# 10_-_Isolation.net
KiCad netlist of a schematic drawn in Altium Designer
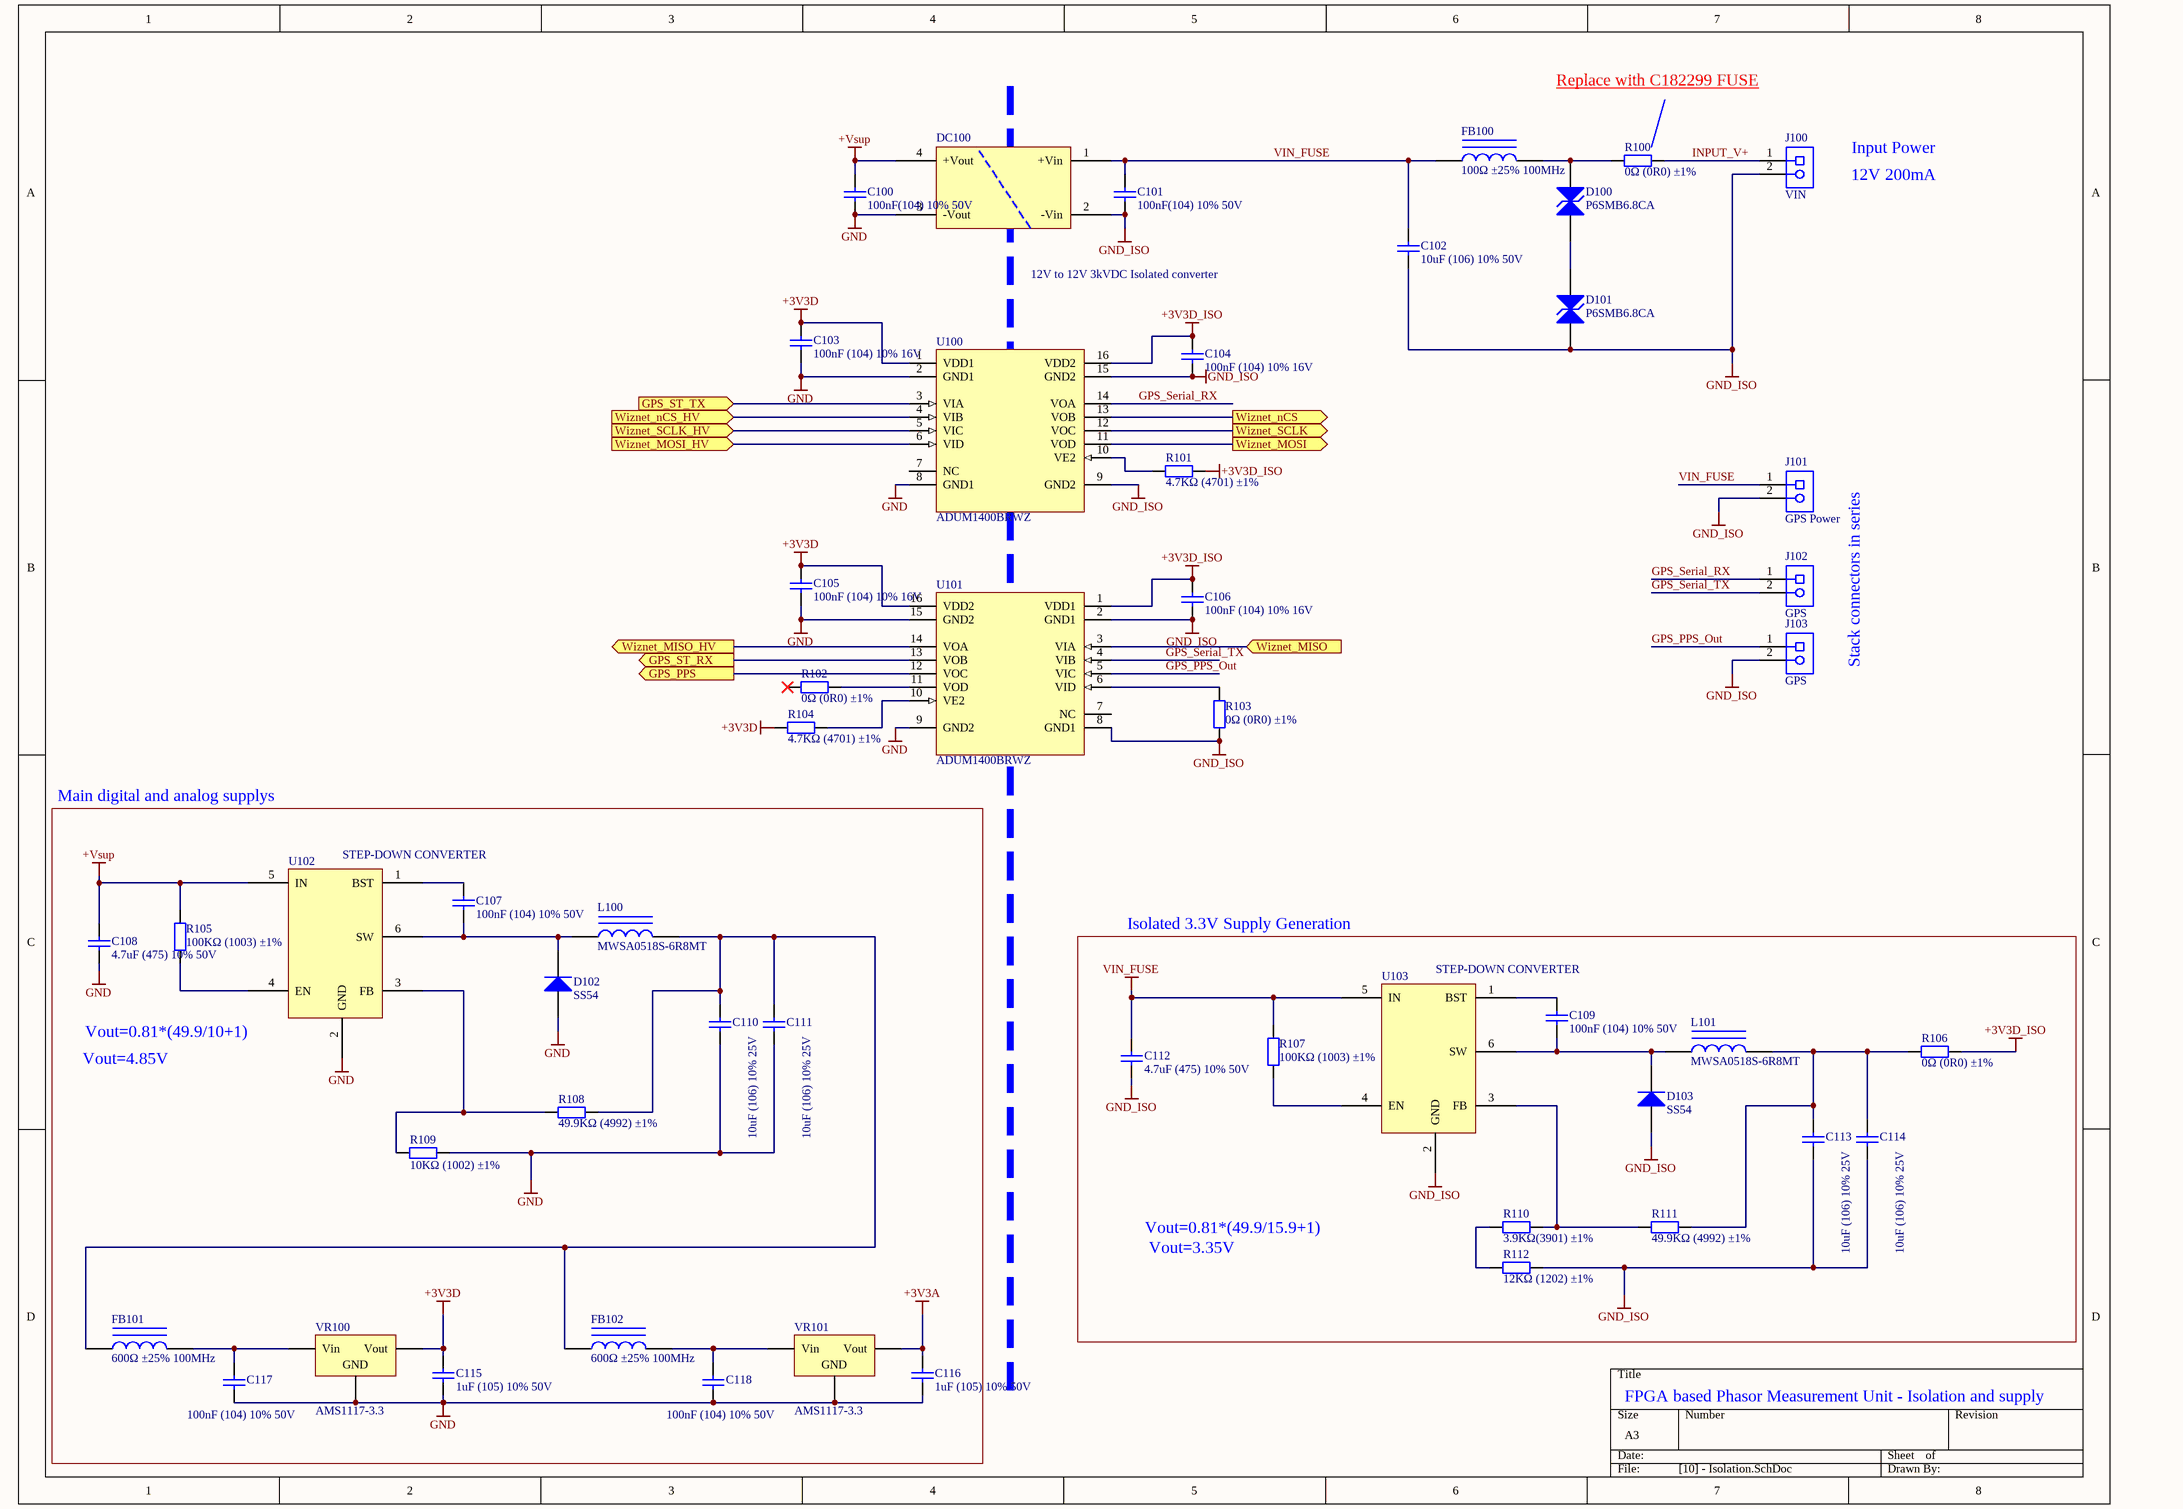
[diagram p0: [10] - Isolation.SchDoc]

(export (version "E")
  (design (tool "Eeschema 10.0.6"))
  (components
    (comp (ref "C100")
      (value "100nF(104) 10% 50V")
      (footprint "0805_C")
      (description "贴片电容")
      (libsource (lib "Cap") (part "0805 100nF(104) 10% 50V"))
    )
    (comp (ref "C101")
      (value "100nF(104) 10% 50V")
      (footprint "0805_C")
      (description "贴片电容")
      (libsource (lib "Cap") (part "0805 100nF(104) 10% 50V"))
    )
    (comp (ref "C102")
      (value "10uF (106) 10% 50V")
      (footprint "1206_C")
      (description "贴片电容")
      (libsource (lib "Cap") (part "1206 10uF (106) 10% 50V"))
    )
    (comp (ref "C103")
      (value "100nF (104) 10% 16V")
      (footprint "0402_C")
      (description "贴片电容")
      (libsource (lib "Cap") (part "0402 100nF (104) 10% 16V"))
    )
    (comp (ref "C104")
      (value "100nF (104) 10% 16V")
      (footprint "0402_C")
      (description "贴片电容")
      (libsource (lib "Cap") (part "0402 100nF (104) 10% 16V"))
    )
    (comp (ref "C105")
      (value "100nF (104) 10% 16V")
      (footprint "0402_C")
      (description "贴片电容")
      (libsource (lib "Cap") (part "0402 100nF (104) 10% 16V"))
    )
    (comp (ref "C106")
      (value "100nF (104) 10% 16V")
      (footprint "0402_C")
      (description "贴片电容")
      (libsource (lib "Cap") (part "0402 100nF (104) 10% 16V"))
    )
    (comp (ref "C107")
      (value "100nF (104) 10% 50V")
      (footprint "0603_C")
      (description "贴片电容")
      (libsource (lib "Cap") (part "0603 100nF (104) 10% 50V"))
    )
    (comp (ref "C108")
      (value "4.7uF (475) 10% 50V")
      (footprint "1206_C")
      (description "贴片电容")
      (libsource (lib "Cap") (part "1206 4.7uF (475) 10% 50V"))
    )
    (comp (ref "C109")
      (value "100nF (104) 10% 50V")
      (footprint "0603_C")
      (description "贴片电容")
      (libsource (lib "Cap") (part "0603 100nF (104) 10% 50V"))
    )
    (comp (ref "C110")
      (value "10uF (106) 10% 25V")
      (footprint "0805_C")
      (description "贴片电容")
      (libsource (lib "Cap") (part "0805 10uF (106) 10% 25V"))
    )
    (comp (ref "C111")
      (value "10uF (106) 10% 25V")
      (footprint "0805_C")
      (description "贴片电容")
      (libsource (lib "Cap") (part "0805 10uF (106) 10% 25V"))
    )
    (comp (ref "C112")
      (value "4.7uF (475) 10% 50V")
      (footprint "1206_C")
      (description "贴片电容")
      (libsource (lib "Cap") (part "1206 4.7uF (475) 10% 50V"))
    )
    (comp (ref "C113")
      (value "10uF (106) 10% 25V")
      (footprint "0805_C")
      (description "贴片电容")
      (libsource (lib "Cap") (part "0805 10uF (106) 10% 25V"))
    )
    (comp (ref "C114")
      (value "10uF (106) 10% 25V")
      (footprint "0805_C")
      (description "贴片电容")
      (libsource (lib "Cap") (part "0805 10uF (106) 10% 25V"))
    )
    (comp (ref "C115")
      (value "1uF (105) 10% 50V")
      (footprint "0603_C")
      (description "贴片电容")
      (libsource (lib "Cap") (part "0603 1uF (105) 10% 50V"))
    )
    (comp (ref "C116")
      (value "1uF (105) 10% 50V")
      (footprint "0603_C")
      (description "贴片电容")
      (libsource (lib "Cap") (part "0603 1uF (105) 10% 50V"))
    )
    (comp (ref "C117")
      (value "100nF (104) 10% 50V")
      (footprint "0603_C")
      (description "贴片电容")
      (libsource (lib "Cap") (part "0603 100nF (104) 10% 50V"))
    )
    (comp (ref "C118")
      (value "100nF (104) 10% 50V")
      (footprint "0603_C")
      (description "贴片电容")
      (libsource (lib "Cap") (part "0603 100nF (104) 10% 50V"))
    )
    (comp (ref "D100")
      (value "P6SMB6.8CA")
      (footprint "SMB(DO-214AA)_S1")
      (description "TVS")
      (libsource (lib "Diode") (part "SMB/DO-214AA P6SMB6.8CA"))
    )
    (comp (ref "D101")
      (value "P6SMB6.8CA")
      (footprint "SMB(DO-214AA)_S1")
      (description "TVS")
      (libsource (lib "Diode") (part "SMB/DO-214AA P6SMB6.8CA"))
    )
    (comp (ref "D102")
      (value "SS54")
      (footprint "SMA(DO-214AC)_S1")
      (description "二极管")
      (libsource (lib "Diode") (part "SMA(DO-214AC) SS54"))
    )
    (comp (ref "D103")
      (value "SS54")
      (footprint "SMA(DO-214AC)_S1")
      (description "二极管")
      (libsource (lib "Diode") (part "SMA(DO-214AC) SS54"))
    )
    (comp (ref "DC100")
      (value "12V to 12V 3kVDC Isolated converter")
      (footprint "SPI-7 DC DC")
      (description "Isolated DC-DC Converters F_S-2W2R Series -- 2Watt")
      (libsource (lib "FPGA_PMU_lib") (part "F1212S-2WR2"))
    )
    (comp (ref "FB100")
      (value "100Ω ±25% 100MHz")
      (footprint "0805_L")
      (description "贴片磁珠")
      (libsource (lib "IUD") (part "0805 100Ω 25% 100MHz"))
    )
    (comp (ref "FB101")
      (value "600Ω ±25% 100MHz")
      (footprint "0805_L")
      (description "贴片磁珠")
      (libsource (lib "IUD") (part "0805 600Ω 25% 100MHz"))
    )
    (comp (ref "FB102")
      (value "600Ω ±25% 100MHz")
      (footprint "0805_L")
      (description "贴片磁珠")
      (libsource (lib "IUD") (part "0805 600Ω 25% 100MHz"))
    )
    (comp (ref "J100")
      (value "VIN")
      (footprint "PHOE-1729128-2_V")
      (description "PCB Terminal Block, 13.5 A, 400 V, 2-Pin THD, RoHS, Bulk")
      (fields (field (name "PARTNUMBER") "1729128") (field (name "MANUFACTURER") "Phoenix Contact"))
      (libsource (lib "Altium Content Vault") (part "CN-2P-F-R2"))
    )
    (comp (ref "J101")
      (value "GPS Power")
      (footprint "PHOE-1729128-2_V")
      (description "PCB Terminal Block, 13.5 A, 400 V, 2-Pin THD, RoHS, Bulk")
      (fields (field (name "PARTNUMBER") "1729128") (field (name "MANUFACTURER") "Phoenix Contact"))
      (libsource (lib "Altium Content Vault") (part "CN-2P-F-R2"))
    )
    (comp (ref "J102")
      (value "GPS")
      (footprint "PHOE-1729128-2_V")
      (description "PCB Terminal Block, 13.5 A, 400 V, 2-Pin THD, RoHS, Bulk")
      (fields (field (name "PARTNUMBER") "1729128") (field (name "MANUFACTURER") "Phoenix Contact"))
      (libsource (lib "Altium Content Vault") (part "CN-2P-F-R2"))
    )
    (comp (ref "J103")
      (value "GPS")
      (footprint "PHOE-1729128-2_V")
      (description "PCB Terminal Block, 13.5 A, 400 V, 2-Pin THD, RoHS, Bulk")
      (fields (field (name "PARTNUMBER") "1729128") (field (name "MANUFACTURER") "Phoenix Contact"))
      (libsource (lib "Altium Content Vault") (part "CN-2P-F-R2"))
    )
    (comp (ref "L100")
      (value "MWSA0518S-6R8MT")
      (footprint "MWSA0518")
      (description "POWER INDUCTORS SMD,5.2X5.4X1.8MM ROHS")
      (libsource (lib "FPGA_PMU_lib") (part "MWSA0518S-6R8MT"))
    )
    (comp (ref "L101")
      (value "MWSA0518S-6R8MT")
      (footprint "MWSA0518")
      (description "POWER INDUCTORS SMD,5.2X5.4X1.8MM ROHS")
      (libsource (lib "FPGA_PMU_lib") (part "MWSA0518S-6R8MT"))
    )
    (comp (ref "R100")
      (value "0Ω (0R0) ±1%")
      (footprint "0603_R")
      (description "贴片电阻")
      (libsource (lib "RES") (part "0603 0Ω (0R0) 1%"))
    )
    (comp (ref "R101")
      (value "4.7KΩ (4701) ±1%")
      (footprint "0402_R")
      (description "贴片电阻")
      (libsource (lib "RES") (part "0402 4.7KΩ (4701) 1%"))
    )
    (comp (ref "R102")
      (value "0Ω (0R0) ±1%")
      (footprint "0402_R")
      (description "贴片电阻")
      (libsource (lib "RES") (part "0402 0Ω (0R0) 1%"))
    )
    (comp (ref "R103")
      (value "0Ω (0R0) ±1%")
      (footprint "0402_R")
      (description "贴片电阻")
      (libsource (lib "") (part "0402 0Ω (0R0) 1%_1"))
    )
    (comp (ref "R104")
      (value "4.7KΩ (4701) ±1%")
      (footprint "0402_R")
      (description "贴片电阻")
      (libsource (lib "RES") (part "0402 4.7KΩ (4701) 1%"))
    )
    (comp (ref "R105")
      (value "100KΩ (1003) ±1%")
      (footprint "0402_R")
      (description "贴片电阻")
      (libsource (lib "RES") (part "0402 100KΩ (1003) 1%"))
    )
    (comp (ref "R106")
      (value "0Ω (0R0) ±1%")
      (footprint "0805_R")
      (description "贴片电阻")
      (libsource (lib "RES") (part "0805 0Ω (0R0) 1%"))
    )
    (comp (ref "R107")
      (value "100KΩ (1003) ±1%")
      (footprint "0402_R")
      (description "贴片电阻")
      (libsource (lib "RES") (part "0402 100KΩ (1003) 1%"))
    )
    (comp (ref "R108")
      (value "49.9KΩ (4992) ±1%")
      (footprint "0402_R")
      (description "贴片电阻")
      (libsource (lib "RES") (part "0402 49.9KΩ (4992) 1%"))
    )
    (comp (ref "R109")
      (value "10KΩ (1002) ±1%")
      (footprint "0402_R")
      (description "贴片电阻")
      (libsource (lib "RES") (part "0402 10KΩ (1002) 1%"))
    )
    (comp (ref "R110")
      (value "3.9KΩ(3901) ±1%")
      (footprint "0402_R")
      (description "贴片电阻")
      (libsource (lib "RES") (part "0402 3.9KΩ(3901) 1%"))
    )
    (comp (ref "R111")
      (value "49.9KΩ (4992) ±1%")
      (footprint "0402_R")
      (description "贴片电阻")
      (libsource (lib "RES") (part "0402 49.9KΩ (4992) 1%"))
    )
    (comp (ref "R112")
      (value "12KΩ (1202) ±1%")
      (footprint "0402_R")
      (description "贴片电阻")
      (libsource (lib "RES") (part "0402 12KΩ (1202) 1%"))
    )
    (comp (ref "U100")
      (value "ADUM1400BRWZ")
      (footprint "ADI-RW-16_L")
      (fields (field (name "MANUFACTURER") "Analog Devices"))
      (libsource (lib "") (part "ADI-ADUMX400-RX-16_1"))
    )
    (comp (ref "U101")
      (value "ADUM1400BRWZ")
      (footprint "ADI-RW-16_L")
      (fields (field (name "MANUFACTURER") "Analog Devices"))
      (libsource (lib "FPGA_PMU_lib") (part "ADI-ADUMX400-RX-16"))
    )
    (comp (ref "U102")
      (value "STEP-DOWN CONVERTER")
      (footprint "*TSOT-23_S6")
      (description "1.2A, 24V, 1.4MHz STEP-DOWN CONVERTER IN A TSOT23-6")
      (libsource (lib "FPGA_PMU_lib") (part "MP2359"))
    )
    (comp (ref "U103")
      (value "STEP-DOWN CONVERTER")
      (footprint "*TSOT-23_S6")
      (description "1.2A, 24V, 1.4MHz STEP-DOWN CONVERTER IN A TSOT23-6")
      (libsource (lib "FPGA_PMU_lib") (part "MP2359"))
    )
    (comp (ref "VR100")
      (value "AMS1117-3.3")
      (footprint "SOT-223")
      (description "低压差线性稳压(LDO)")
      (libsource (lib "LDO") (part "SOT-223 AMS1117-3.3"))
    )
    (comp (ref "VR101")
      (value "AMS1117-3.3")
      (footprint "SOT-223")
      (description "低压差线性稳压(LDO)")
      (libsource (lib "LDO") (part "SOT-223 AMS1117-3.3"))
    )
  )
  (nets
    (net (code "1") (name "+3V3A") (class "Default")
      (node (ref "C116") (pin "2") (pinfunction "2_2") (pintype "passive"))
      (node (ref "VR101") (pin "2") (pinfunction "Vout_2") (pintype "passive"))
    )
    (net (code "2") (name "+3V3D") (class "Default")
      (node (ref "C103") (pin "2") (pinfunction "2_2") (pintype "passive"))
      (node (ref "C105") (pin "2") (pinfunction "2_2") (pintype "passive"))
      (node (ref "C115") (pin "2") (pinfunction "2_2") (pintype "passive"))
      (node (ref "R104") (pin "1") (pinfunction "1_1") (pintype "passive"))
      (node (ref "U100") (pin "1") (pinfunction "VDD1_1") (pintype "power_in"))
      (node (ref "U101") (pin "16") (pinfunction "VDD2_16") (pintype "power_in"))
      (node (ref "VR100") (pin "2") (pinfunction "Vout_2") (pintype "passive"))
    )
    (net (code "3") (name "+3V3D_ISO") (class "Default")
      (node (ref "C104") (pin "2") (pinfunction "2_2") (pintype "passive"))
      (node (ref "C106") (pin "2") (pinfunction "2_2") (pintype "passive"))
      (node (ref "R101") (pin "2") (pinfunction "2_2") (pintype "passive"))
      (node (ref "R106") (pin "2") (pinfunction "2_2") (pintype "passive"))
      (node (ref "U100") (pin "16") (pinfunction "VDD2_16") (pintype "power_in"))
      (node (ref "U101") (pin "1") (pinfunction "VDD1_1") (pintype "power_in"))
    )
    (net (code "4") (name "+Vsup") (class "Default")
      (node (ref "C100") (pin "2") (pinfunction "2_2") (pintype "passive"))
      (node (ref "C108") (pin "2") (pinfunction "2_2") (pintype "passive"))
      (node (ref "DC100") (pin "4") (pinfunction "+Vout_4") (pintype "passive"))
      (node (ref "R105") (pin "2") (pinfunction "2_2") (pintype "passive"))
      (node (ref "U102") (pin "5") (pinfunction "IN_5") (pintype "passive"))
    )
    (net (code "5") (name "/GPS_PPS") (class "Default")
      (node (ref "U101") (pin "12") (pinfunction "VOC_12") (pintype "tri_state"))
    )
    (net (code "6") (name "/GPS_PPS_Out") (class "Default")
      (node (ref "J103") (pin "1") (pinfunction "1_1") (pintype "passive"))
      (node (ref "U101") (pin "5") (pinfunction "VIC_5") (pintype "input"))
    )
    (net (code "7") (name "/GPS_ST_RX") (class "Default")
      (node (ref "U101") (pin "13") (pinfunction "VOB_13") (pintype "tri_state"))
    )
    (net (code "8") (name "/GPS_ST_TX") (class "Default")
      (node (ref "U100") (pin "3") (pinfunction "VIA_3") (pintype "input"))
    )
    (net (code "9") (name "/GPS_Serial_RX") (class "Default")
      (node (ref "J102") (pin "1") (pinfunction "1_1") (pintype "passive"))
      (node (ref "U100") (pin "14") (pinfunction "VOA_14") (pintype "tri_state"))
    )
    (net (code "10") (name "/GPS_Serial_TX") (class "Default")
      (node (ref "J102") (pin "2") (pinfunction "2_2") (pintype "passive"))
      (node (ref "U101") (pin "4") (pinfunction "VIB_4") (pintype "input"))
    )
    (net (code "11") (name "/INPUT_V+") (class "Default")
      (node (ref "J100") (pin "1") (pinfunction "1_1") (pintype "passive"))
      (node (ref "R100") (pin "2") (pinfunction "2_2") (pintype "passive"))
    )
    (net (code "12") (name "/Wiznet_MISO") (class "Default")
      (node (ref "U101") (pin "3") (pinfunction "VIA_3") (pintype "input"))
    )
    (net (code "13") (name "/Wiznet_MISO_HV") (class "Default")
      (node (ref "U101") (pin "14") (pinfunction "VOA_14") (pintype "tri_state"))
    )
    (net (code "14") (name "/Wiznet_MOSI") (class "Default")
      (node (ref "U100") (pin "11") (pinfunction "VOD_11") (pintype "tri_state"))
    )
    (net (code "15") (name "/Wiznet_MOSI_HV") (class "Default")
      (node (ref "U100") (pin "6") (pinfunction "VID_6") (pintype "input"))
    )
    (net (code "16") (name "/Wiznet_SCLK") (class "Default")
      (node (ref "U100") (pin "12") (pinfunction "VOC_12") (pintype "tri_state"))
    )
    (net (code "17") (name "/Wiznet_SCLK_HV") (class "Default")
      (node (ref "U100") (pin "5") (pinfunction "VIC_5") (pintype "input"))
    )
    (net (code "18") (name "/Wiznet_nCS") (class "Default")
      (node (ref "U100") (pin "13") (pinfunction "VOB_13") (pintype "tri_state"))
    )
    (net (code "19") (name "/Wiznet_nCS_HV") (class "Default")
      (node (ref "U100") (pin "4") (pinfunction "VIB_4") (pintype "input"))
    )
    (net (code "20") (name "GND") (class "Default")
      (node (ref "C100") (pin "1") (pinfunction "1_1") (pintype "passive"))
      (node (ref "C103") (pin "1") (pinfunction "1_1") (pintype "passive"))
      (node (ref "C105") (pin "1") (pinfunction "1_1") (pintype "passive"))
      (node (ref "C108") (pin "1") (pinfunction "1_1") (pintype "passive"))
      (node (ref "C110") (pin "1") (pinfunction "1_1") (pintype "passive"))
      (node (ref "C111") (pin "1") (pinfunction "1_1") (pintype "passive"))
      (node (ref "C115") (pin "1") (pinfunction "1_1") (pintype "passive"))
      (node (ref "C116") (pin "1") (pinfunction "1_1") (pintype "passive"))
      (node (ref "C117") (pin "1") (pinfunction "1_1") (pintype "passive"))
      (node (ref "C118") (pin "1") (pinfunction "1_1") (pintype "passive"))
      (node (ref "D102") (pin "1") (pinfunction "A_1") (pintype "passive"))
      (node (ref "DC100") (pin "3") (pinfunction "-Vout_3") (pintype "passive"))
      (node (ref "R109") (pin "2") (pinfunction "2_2") (pintype "passive"))
      (node (ref "U100") (pin "2") (pinfunction "GND1_2") (pintype "power_in"))
      (node (ref "U100") (pin "8") (pinfunction "GND1_8") (pintype "power_in"))
      (node (ref "U101") (pin "15") (pinfunction "GND2_15") (pintype "power_in"))
      (node (ref "U101") (pin "9") (pinfunction "GND2_9") (pintype "power_in"))
      (node (ref "U102") (pin "2") (pinfunction "GND_2") (pintype "passive"))
      (node (ref "VR100") (pin "1") (pinfunction "GND_1") (pintype "passive"))
      (node (ref "VR101") (pin "1") (pinfunction "GND_1") (pintype "passive"))
    )
    (net (code "21") (name "GND_ISO") (class "Default")
      (node (ref "C101") (pin "1") (pinfunction "1_1") (pintype "passive"))
      (node (ref "C102") (pin "1") (pinfunction "1_1") (pintype "passive"))
      (node (ref "C104") (pin "1") (pinfunction "1_1") (pintype "passive"))
      (node (ref "C106") (pin "1") (pinfunction "1_1") (pintype "passive"))
      (node (ref "C112") (pin "1") (pinfunction "1_1") (pintype "passive"))
      (node (ref "C113") (pin "1") (pinfunction "1_1") (pintype "passive"))
      (node (ref "C114") (pin "1") (pinfunction "1_1") (pintype "passive"))
      (node (ref "D101") (pin "1") (pinfunction "A_1") (pintype "passive"))
      (node (ref "D103") (pin "1") (pinfunction "A_1") (pintype "passive"))
      (node (ref "DC100") (pin "2") (pinfunction "-Vin_2") (pintype "passive"))
      (node (ref "J100") (pin "2") (pinfunction "2_2") (pintype "passive"))
      (node (ref "J101") (pin "2") (pinfunction "2_2") (pintype "passive"))
      (node (ref "J103") (pin "2") (pinfunction "2_2") (pintype "passive"))
      (node (ref "R103") (pin "1") (pinfunction "1_1") (pintype "passive"))
      (node (ref "R112") (pin "2") (pinfunction "2_2") (pintype "passive"))
      (node (ref "U100") (pin "15") (pinfunction "GND2_15") (pintype "power_in"))
      (node (ref "U100") (pin "9") (pinfunction "GND2_9") (pintype "power_in"))
      (node (ref "U101") (pin "2") (pinfunction "GND1_2") (pintype "power_in"))
      (node (ref "U101") (pin "8") (pinfunction "GND1_8") (pintype "power_in"))
      (node (ref "U103") (pin "2") (pinfunction "GND_2") (pintype "passive"))
    )
    (net (code "22") (name "Net-(C110-Pad2)") (class "Default")
      (node (ref "C110") (pin "2") (pinfunction "2_2") (pintype "passive"))
      (node (ref "C111") (pin "2") (pinfunction "2_2") (pintype "passive"))
      (node (ref "FB101") (pin "1") (pinfunction "1_1") (pintype "passive"))
      (node (ref "FB102") (pin "1") (pinfunction "1_1") (pintype "passive"))
      (node (ref "L100") (pin "2") (pinfunction "2_2") (pintype "power_in"))
      (node (ref "R108") (pin "2") (pinfunction "2_2") (pintype "passive"))
    )
    (net (code "23") (name "Net-(C113-Pad2)") (class "Default")
      (node (ref "C113") (pin "2") (pinfunction "2_2") (pintype "passive"))
      (node (ref "C114") (pin "2") (pinfunction "2_2") (pintype "passive"))
      (node (ref "L101") (pin "2") (pinfunction "2_2") (pintype "power_in"))
      (node (ref "R106") (pin "1") (pinfunction "1_1") (pintype "passive"))
      (node (ref "R111") (pin "2") (pinfunction "2_2") (pintype "passive"))
    )
    (net (code "24") (name "Net-(D100-A)") (class "Default")
      (node (ref "D100") (pin "1") (pinfunction "A_1") (pintype "passive"))
      (node (ref "D101") (pin "2") (pinfunction "K_2") (pintype "passive"))
    )
    (net (code "25") (name "Net-(D100-K)") (class "Default")
      (node (ref "D100") (pin "2") (pinfunction "K_2") (pintype "passive"))
      (node (ref "FB100") (pin "2") (pinfunction "2_2") (pintype "passive"))
      (node (ref "R100") (pin "1") (pinfunction "1_1") (pintype "passive"))
    )
    (net (code "26") (name "Net-(D102-K)") (class "Default")
      (node (ref "C107") (pin "1") (pinfunction "1_1") (pintype "passive"))
      (node (ref "D102") (pin "2") (pinfunction "K_2") (pintype "passive"))
      (node (ref "L100") (pin "1") (pinfunction "1_1") (pintype "power_in"))
      (node (ref "U102") (pin "6") (pinfunction "SW_6") (pintype "passive"))
    )
    (net (code "27") (name "Net-(D103-K)") (class "Default")
      (node (ref "C109") (pin "1") (pinfunction "1_1") (pintype "passive"))
      (node (ref "D103") (pin "2") (pinfunction "K_2") (pintype "passive"))
      (node (ref "L101") (pin "1") (pinfunction "1_1") (pintype "power_in"))
      (node (ref "U103") (pin "6") (pinfunction "SW_6") (pintype "passive"))
    )
    (net (code "28") (name "Net-(R110-Pad1)") (class "Default")
      (node (ref "R110") (pin "1") (pinfunction "1_1") (pintype "passive"))
      (node (ref "R112") (pin "1") (pinfunction "1_1") (pintype "passive"))
    )
    (net (code "29") (name "Net-(U100-VE2)") (class "Default")
      (node (ref "R101") (pin "1") (pinfunction "1_1") (pintype "passive"))
      (node (ref "U100") (pin "10") (pinfunction "VE2_10") (pintype "input"))
    )
    (net (code "30") (name "Net-(U101-VE2)") (class "Default")
      (node (ref "R104") (pin "2") (pinfunction "2_2") (pintype "passive"))
      (node (ref "U101") (pin "10") (pinfunction "VE2_10") (pintype "input"))
    )
    (net (code "31") (name "Net-(U101-VID)") (class "Default")
      (node (ref "R103") (pin "2") (pinfunction "2_2") (pintype "passive"))
      (node (ref "U101") (pin "6") (pinfunction "VID_6") (pintype "input"))
    )
    (net (code "32") (name "Net-(U101-VOD)") (class "Default")
      (node (ref "R102") (pin "1") (pinfunction "1_1") (pintype "passive"))
      (node (ref "U101") (pin "11") (pinfunction "VOD_11") (pintype "tri_state"))
    )
    (net (code "33") (name "Net-(U102-BST)") (class "Default")
      (node (ref "C107") (pin "2") (pinfunction "2_2") (pintype "passive"))
      (node (ref "U102") (pin "1") (pinfunction "BST_1") (pintype "passive"))
    )
    (net (code "34") (name "Net-(U102-EN)") (class "Default")
      (node (ref "R105") (pin "1") (pinfunction "1_1") (pintype "passive"))
      (node (ref "U102") (pin "4") (pinfunction "EN_4") (pintype "passive"))
    )
    (net (code "35") (name "Net-(U102-FB)") (class "Default")
      (node (ref "R108") (pin "1") (pinfunction "1_1") (pintype "passive"))
      (node (ref "R109") (pin "1") (pinfunction "1_1") (pintype "passive"))
      (node (ref "U102") (pin "3") (pinfunction "FB_3") (pintype "passive"))
    )
    (net (code "36") (name "Net-(U103-BST)") (class "Default")
      (node (ref "C109") (pin "2") (pinfunction "2_2") (pintype "passive"))
      (node (ref "U103") (pin "1") (pinfunction "BST_1") (pintype "passive"))
    )
    (net (code "37") (name "Net-(U103-EN)") (class "Default")
      (node (ref "R107") (pin "1") (pinfunction "1_1") (pintype "passive"))
      (node (ref "U103") (pin "4") (pinfunction "EN_4") (pintype "passive"))
    )
    (net (code "38") (name "Net-(U103-FB)") (class "Default")
      (node (ref "R110") (pin "2") (pinfunction "2_2") (pintype "passive"))
      (node (ref "R111") (pin "1") (pinfunction "1_1") (pintype "passive"))
      (node (ref "U103") (pin "3") (pinfunction "FB_3") (pintype "passive"))
    )
    (net (code "39") (name "Net-(VR100-Vin)") (class "Default")
      (node (ref "C117") (pin "2") (pinfunction "2_2") (pintype "passive"))
      (node (ref "FB101") (pin "2") (pinfunction "2_2") (pintype "passive"))
      (node (ref "VR100") (pin "3") (pinfunction "Vin_3") (pintype "passive"))
    )
    (net (code "40") (name "Net-(VR101-Vin)") (class "Default")
      (node (ref "C118") (pin "2") (pinfunction "2_2") (pintype "passive"))
      (node (ref "FB102") (pin "2") (pinfunction "2_2") (pintype "passive"))
      (node (ref "VR101") (pin "3") (pinfunction "Vin_3") (pintype "passive"))
    )
    (net (code "41") (name "VIN_FUSE") (class "Default")
      (node (ref "C101") (pin "2") (pinfunction "2_2") (pintype "passive"))
      (node (ref "C102") (pin "2") (pinfunction "2_2") (pintype "passive"))
      (node (ref "C112") (pin "2") (pinfunction "2_2") (pintype "passive"))
      (node (ref "DC100") (pin "1") (pinfunction "+Vin_1") (pintype "passive"))
      (node (ref "FB100") (pin "1") (pinfunction "1_1") (pintype "passive"))
      (node (ref "J101") (pin "1") (pinfunction "1_1") (pintype "passive"))
      (node (ref "R107") (pin "2") (pinfunction "2_2") (pintype "passive"))
      (node (ref "U103") (pin "5") (pinfunction "IN_5") (pintype "passive"))
    )
    (net (code "42") (name "unconnected-(R102-Pad2)") (class "Default")
      (node (ref "R102") (pin "2") (pinfunction "2_2") (pintype "passive+no_connect"))
    )
    (net (code "43") (name "unconnected-(U100-NC-Pad7)") (class "Default")
      (node (ref "U100") (pin "7") (pinfunction "NC_7") (pintype "passive"))
    )
    (net (code "44") (name "unconnected-(U101-NC-Pad7)") (class "Default")
      (node (ref "U101") (pin "7") (pinfunction "NC_7") (pintype "passive"))
    )
  )
)
